# SATELLITE_SIMPLE.net
KiCad netlist of a schematic drawn in EAGLE
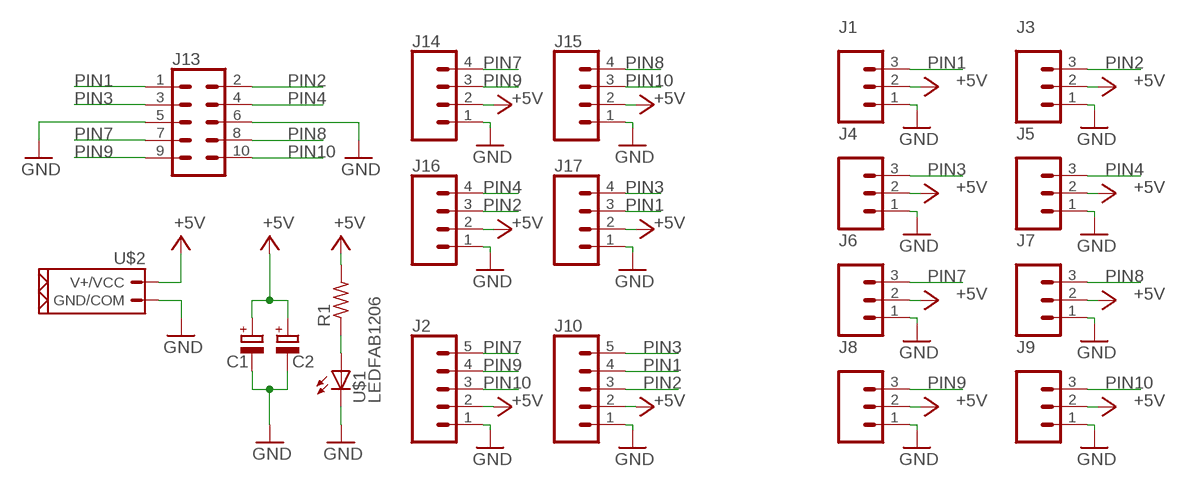
[diagram p0: schematic, sheet 1]

(export (version "E")
  (design (tool "Eeschema 10.0.6"))
  (components
    (comp (ref "C1")
      (value "CPOL-EUE5-10.5")
      (footprint "eagle-import:E5-10,5")
      (libsource (lib "eagle-import") (part "CPOL-EUE5-10.5"))
    )
    (comp (ref "C2")
      (value "CPOL-EUE5-10.5")
      (footprint "eagle-import:E5-10,5")
      (libsource (lib "eagle-import") (part "CPOL-EUE5-10.5"))
    )
    (comp (ref "J1")
      (value "CONN_03POLAR")
      (footprint "eagle-import:MOLEX-1X3")
      (libsource (lib "eagle-import") (part "CONN_03POLAR"))
    )
    (comp (ref "J2")
      (value "CONN_05")
      (footprint "eagle-import:MOLEX-1X5")
      (libsource (lib "eagle-import") (part "CONN_05"))
    )
    (comp (ref "J3")
      (value "CONN_03POLAR")
      (footprint "eagle-import:MOLEX-1X3")
      (libsource (lib "eagle-import") (part "CONN_03POLAR"))
    )
    (comp (ref "J4")
      (value "CONN_03POLAR")
      (footprint "eagle-import:MOLEX-1X3")
      (libsource (lib "eagle-import") (part "CONN_03POLAR"))
    )
    (comp (ref "J5")
      (value "CONN_03POLAR")
      (footprint "eagle-import:MOLEX-1X3")
      (libsource (lib "eagle-import") (part "CONN_03POLAR"))
    )
    (comp (ref "J6")
      (value "CONN_03POLAR")
      (footprint "eagle-import:MOLEX-1X3")
      (libsource (lib "eagle-import") (part "CONN_03POLAR"))
    )
    (comp (ref "J7")
      (value "CONN_03POLAR")
      (footprint "eagle-import:MOLEX-1X3")
      (libsource (lib "eagle-import") (part "CONN_03POLAR"))
    )
    (comp (ref "J8")
      (value "CONN_03POLAR")
      (footprint "eagle-import:MOLEX-1X3")
      (libsource (lib "eagle-import") (part "CONN_03POLAR"))
    )
    (comp (ref "J9")
      (value "CONN_03POLAR")
      (footprint "eagle-import:MOLEX-1X3")
      (libsource (lib "eagle-import") (part "CONN_03POLAR"))
    )
    (comp (ref "J10")
      (value "CONN_05")
      (footprint "eagle-import:MOLEX-1X5")
      (libsource (lib "eagle-import") (part "CONN_05"))
    )
    (comp (ref "J13")
      (value "CONN_05X2SHD")
      (footprint "eagle-import:2X5-SHROUDED")
      (libsource (lib "eagle-import") (part "CONN_05X2SHD"))
    )
    (comp (ref "J14")
      (value "CONN_04POLAR")
      (footprint "eagle-import:MOLEX-1X4")
      (libsource (lib "eagle-import") (part "CONN_04POLAR"))
    )
    (comp (ref "J15")
      (value "CONN_04POLAR")
      (footprint "eagle-import:MOLEX-1X4")
      (libsource (lib "eagle-import") (part "CONN_04POLAR"))
    )
    (comp (ref "J16")
      (value "CONN_04POLAR")
      (footprint "eagle-import:MOLEX-1X4")
      (libsource (lib "eagle-import") (part "CONN_04POLAR"))
    )
    (comp (ref "J17")
      (value "CONN_04POLAR")
      (footprint "eagle-import:MOLEX-1X4")
      (libsource (lib "eagle-import") (part "CONN_04POLAR"))
    )
    (comp (ref "R1")
      (value "RES-US1206FAB")
      (footprint "eagle-import:R1206FAB")
      (libsource (lib "eagle-import") (part "RES-US1206FAB"))
    )
    (comp (ref "U$1")
      (value "LEDFAB1206")
      (footprint "eagle-import:LED1206FAB")
      (libsource (lib "eagle-import") (part "LEDFAB1206"))
    )
    (comp (ref "U$2")
      (value "CONN_02_PUI")
      (footprint "eagle-import:NSK396-2C")
      (libsource (lib "eagle-import") (part "CONN_02_PUI"))
    )
  )
  (nets
    (net (code "1") (name "+5V") (class "Default")
      (node (ref "C1") (pin "+") (pinfunction "+_+") (pintype "passive"))
      (node (ref "C2") (pin "+") (pinfunction "+_+") (pintype "passive"))
      (node (ref "J1") (pin "2") (pinfunction "2_2") (pintype "passive"))
      (node (ref "J10") (pin "2") (pinfunction "2_2") (pintype "passive"))
      (node (ref "J14") (pin "2") (pinfunction "2_2") (pintype "passive"))
      (node (ref "J15") (pin "2") (pinfunction "2_2") (pintype "passive"))
      (node (ref "J16") (pin "2") (pinfunction "2_2") (pintype "passive"))
      (node (ref "J17") (pin "2") (pinfunction "2_2") (pintype "passive"))
      (node (ref "J2") (pin "2") (pinfunction "2_2") (pintype "passive"))
      (node (ref "J3") (pin "2") (pinfunction "2_2") (pintype "passive"))
      (node (ref "J4") (pin "2") (pinfunction "2_2") (pintype "passive"))
      (node (ref "J5") (pin "2") (pinfunction "2_2") (pintype "passive"))
      (node (ref "J6") (pin "2") (pinfunction "2_2") (pintype "passive"))
      (node (ref "J7") (pin "2") (pinfunction "2_2") (pintype "passive"))
      (node (ref "J8") (pin "2") (pinfunction "2_2") (pintype "passive"))
      (node (ref "J9") (pin "2") (pinfunction "2_2") (pintype "passive"))
      (node (ref "R1") (pin "2") (pinfunction "2_2") (pintype "passive"))
      (node (ref "U$2") (pin "P$2") (pinfunction "V+/VCC_P$2") (pintype "passive"))
    )
    (net (code "2") (name "/PIN1") (class "Default")
      (node (ref "J1") (pin "3") (pinfunction "3_3") (pintype "passive"))
      (node (ref "J10") (pin "4") (pinfunction "4_4") (pintype "passive"))
      (node (ref "J13") (pin "1") (pinfunction "1_1") (pintype "passive"))
      (node (ref "J17") (pin "3") (pinfunction "3_3") (pintype "passive"))
    )
    (net (code "3") (name "/PIN2") (class "Default")
      (node (ref "J10") (pin "3") (pinfunction "3_3") (pintype "passive"))
      (node (ref "J13") (pin "2") (pinfunction "2_2") (pintype "passive"))
      (node (ref "J16") (pin "3") (pinfunction "3_3") (pintype "passive"))
      (node (ref "J3") (pin "3") (pinfunction "3_3") (pintype "passive"))
    )
    (net (code "4") (name "/PIN3") (class "Default")
      (node (ref "J10") (pin "5") (pinfunction "5_5") (pintype "passive"))
      (node (ref "J13") (pin "3") (pinfunction "3_3") (pintype "passive"))
      (node (ref "J17") (pin "4") (pinfunction "4_4") (pintype "passive"))
      (node (ref "J4") (pin "3") (pinfunction "3_3") (pintype "passive"))
    )
    (net (code "5") (name "/PIN4") (class "Default")
      (node (ref "J13") (pin "4") (pinfunction "4_4") (pintype "passive"))
      (node (ref "J16") (pin "4") (pinfunction "4_4") (pintype "passive"))
      (node (ref "J5") (pin "3") (pinfunction "3_3") (pintype "passive"))
    )
    (net (code "6") (name "/PIN7") (class "Default")
      (node (ref "J13") (pin "7") (pinfunction "7_7") (pintype "passive"))
      (node (ref "J14") (pin "4") (pinfunction "4_4") (pintype "passive"))
      (node (ref "J2") (pin "5") (pinfunction "5_5") (pintype "passive"))
      (node (ref "J6") (pin "3") (pinfunction "3_3") (pintype "passive"))
    )
    (net (code "7") (name "/PIN8") (class "Default")
      (node (ref "J13") (pin "8") (pinfunction "8_8") (pintype "passive"))
      (node (ref "J15") (pin "4") (pinfunction "4_4") (pintype "passive"))
      (node (ref "J7") (pin "3") (pinfunction "3_3") (pintype "passive"))
    )
    (net (code "8") (name "/PIN9") (class "Default")
      (node (ref "J13") (pin "9") (pinfunction "9_9") (pintype "passive"))
      (node (ref "J14") (pin "3") (pinfunction "3_3") (pintype "passive"))
      (node (ref "J2") (pin "4") (pinfunction "4_4") (pintype "passive"))
      (node (ref "J8") (pin "3") (pinfunction "3_3") (pintype "passive"))
    )
    (net (code "9") (name "/PIN10") (class "Default")
      (node (ref "J13") (pin "10") (pinfunction "10_10") (pintype "passive"))
      (node (ref "J15") (pin "3") (pinfunction "3_3") (pintype "passive"))
      (node (ref "J2") (pin "3") (pinfunction "3_3") (pintype "passive"))
      (node (ref "J9") (pin "3") (pinfunction "3_3") (pintype "passive"))
    )
    (net (code "10") (name "GND") (class "Default")
      (node (ref "C1") (pin "-") (pinfunction "-_-") (pintype "passive"))
      (node (ref "C2") (pin "-") (pinfunction "-_-") (pintype "passive"))
      (node (ref "J1") (pin "1") (pinfunction "1_1") (pintype "passive"))
      (node (ref "J10") (pin "1") (pinfunction "1_1") (pintype "passive"))
      (node (ref "J13") (pin "5") (pinfunction "5_5") (pintype "passive"))
      (node (ref "J13") (pin "6") (pinfunction "6_6") (pintype "passive"))
      (node (ref "J14") (pin "1") (pinfunction "1_1") (pintype "passive"))
      (node (ref "J15") (pin "1") (pinfunction "1_1") (pintype "passive"))
      (node (ref "J16") (pin "1") (pinfunction "1_1") (pintype "passive"))
      (node (ref "J17") (pin "1") (pinfunction "1_1") (pintype "passive"))
      (node (ref "J2") (pin "1") (pinfunction "1_1") (pintype "passive"))
      (node (ref "J3") (pin "1") (pinfunction "1_1") (pintype "passive"))
      (node (ref "J4") (pin "1") (pinfunction "1_1") (pintype "passive"))
      (node (ref "J5") (pin "1") (pinfunction "1_1") (pintype "passive"))
      (node (ref "J6") (pin "1") (pinfunction "1_1") (pintype "passive"))
      (node (ref "J7") (pin "1") (pinfunction "1_1") (pintype "passive"))
      (node (ref "J8") (pin "1") (pinfunction "1_1") (pintype "passive"))
      (node (ref "J9") (pin "1") (pinfunction "1_1") (pintype "passive"))
      (node (ref "U$1") (pin "2") (pinfunction "C_2") (pintype "passive"))
      (node (ref "U$2") (pin "P$1") (pinfunction "GND/COM_P$1") (pintype "passive"))
    )
    (net (code "11") (name "Net-(U$1-A)") (class "Default")
      (node (ref "R1") (pin "1") (pinfunction "1_1") (pintype "passive"))
      (node (ref "U$1") (pin "1") (pinfunction "A_1") (pintype "passive"))
    )
  )
)
